# SCH_Orcon_MV_Control_2023-08-23.net
KiCad netlist of a schematic drawn in EasyEDA
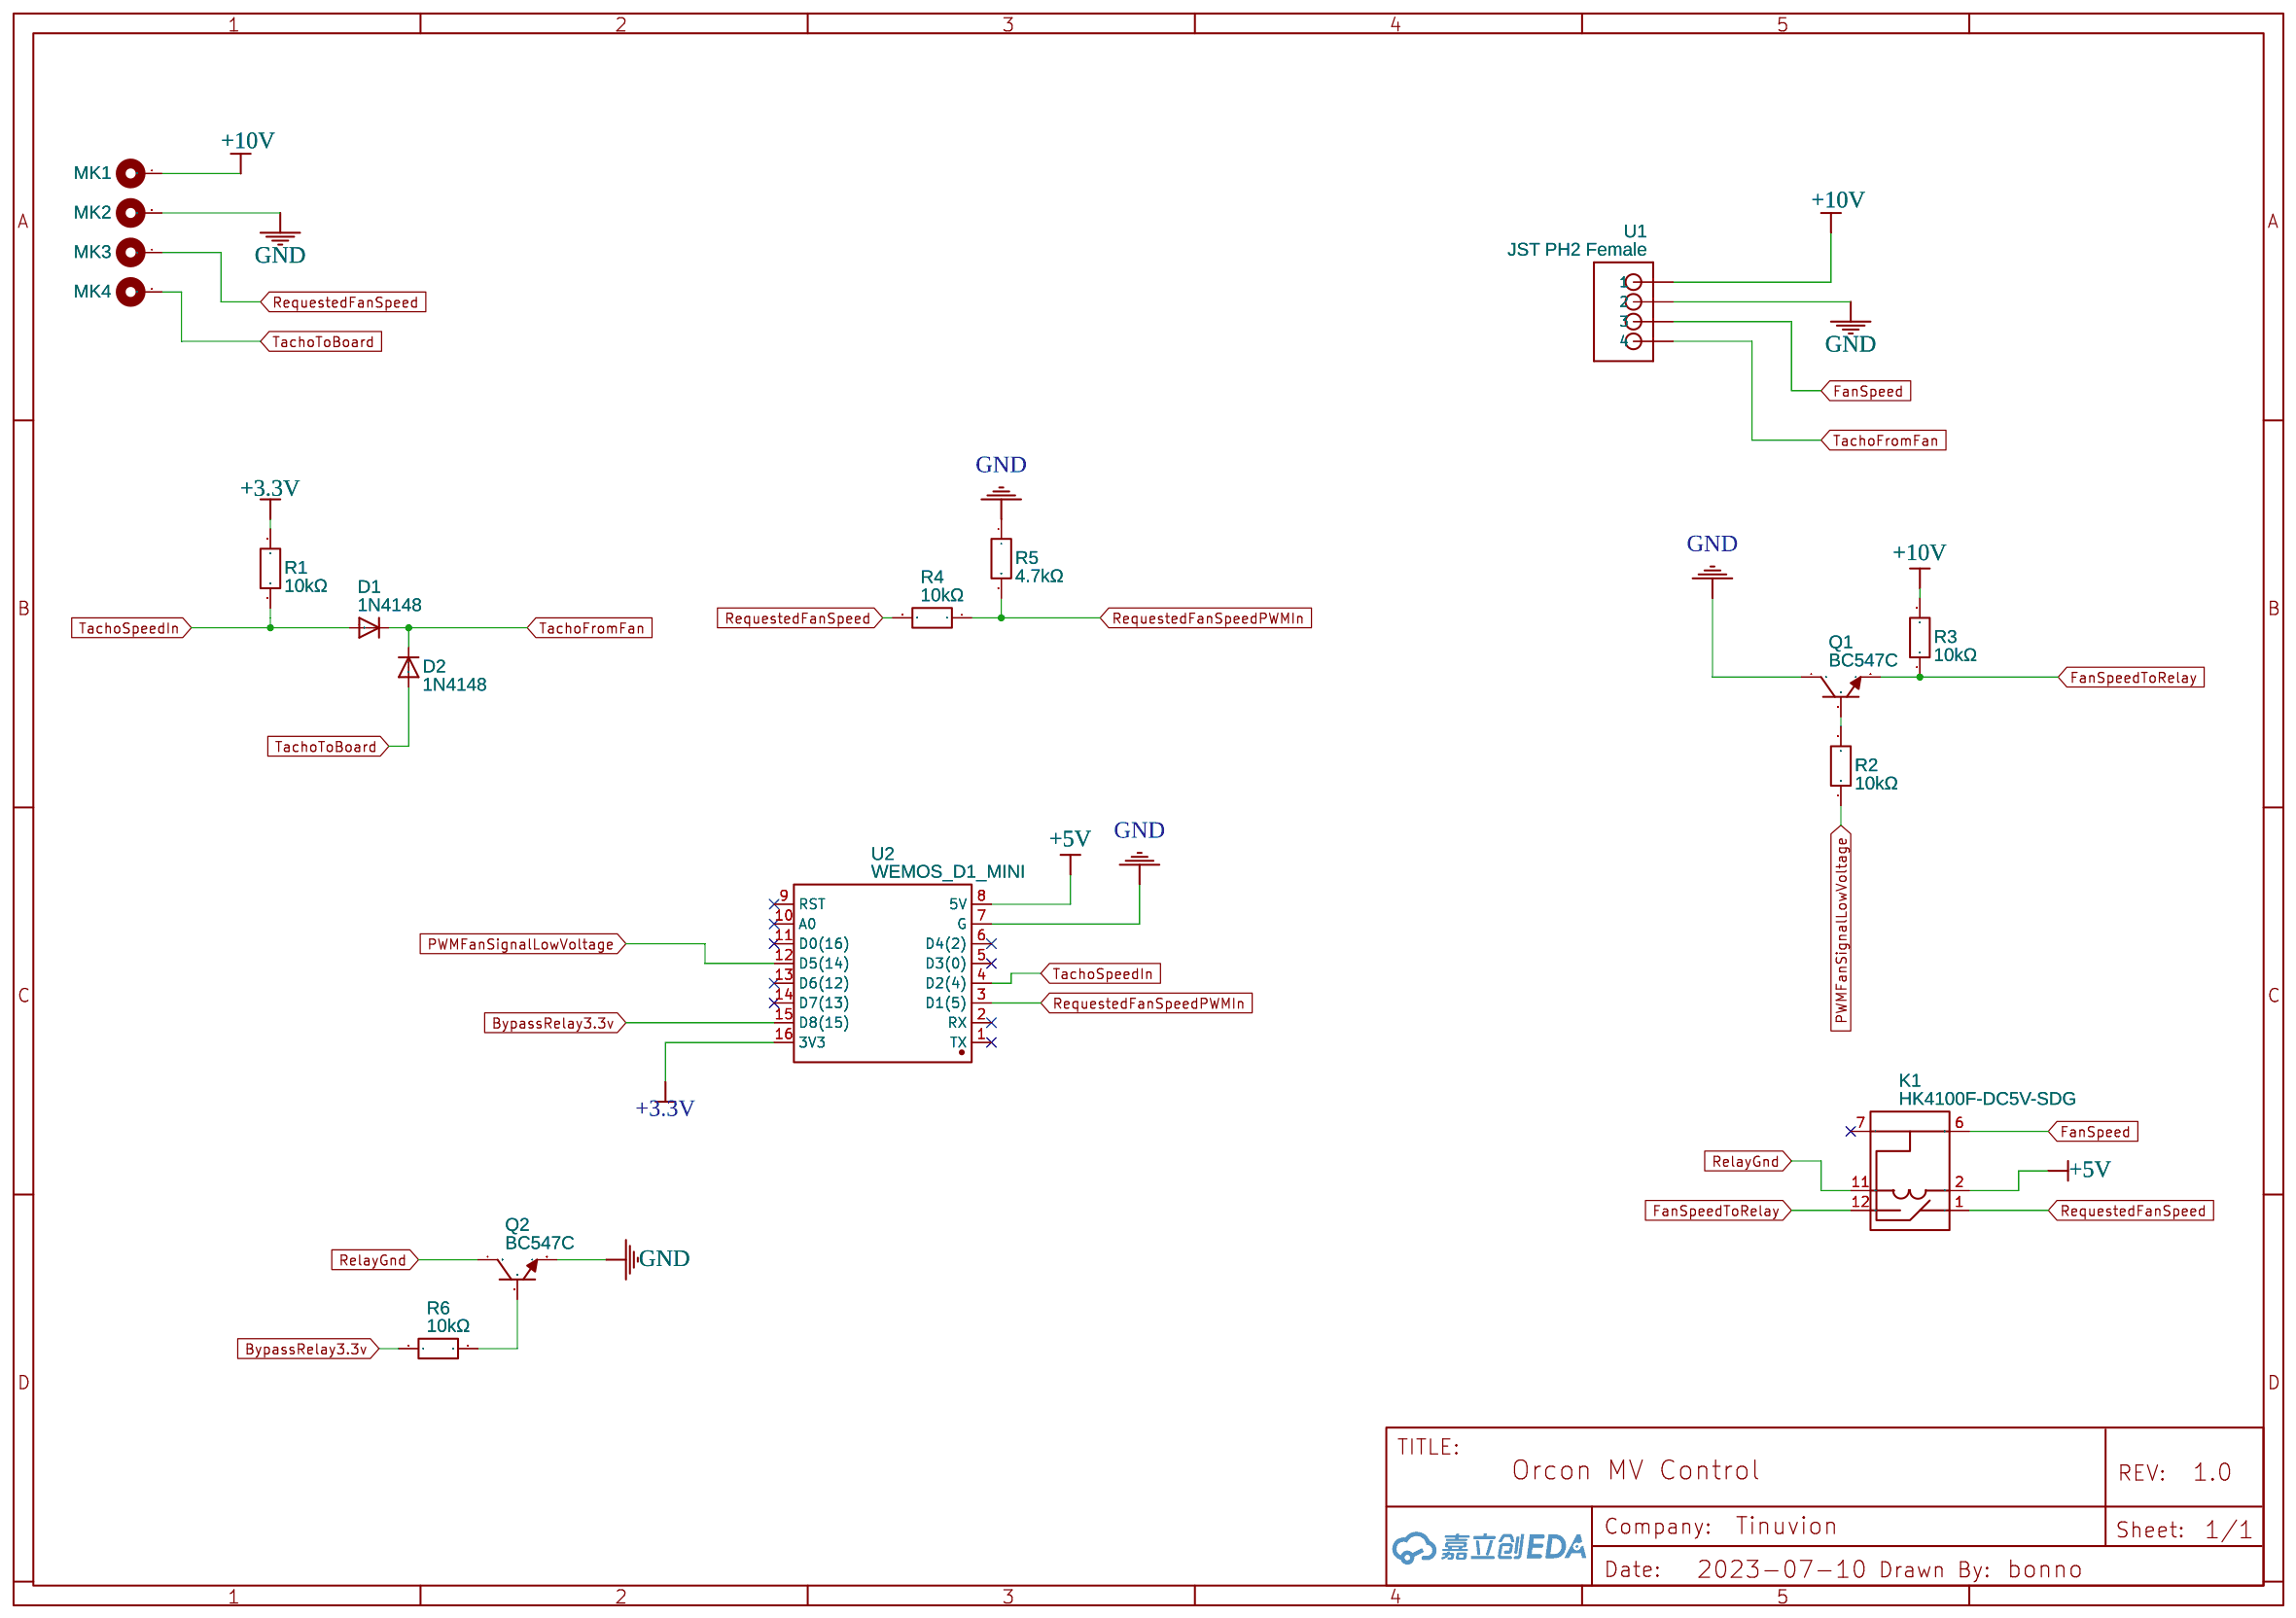
[diagram p0: schematic sheet]

(export (version "E")
  (design (tool "Eeschema 10.0.6"))
  (components
    (comp (ref "D1")
      (value "1N4148")
      (fields (field (name "Manufacturer") "ST(先科)"))
      (libsource (lib "") (part "DIODE_1"))
    )
    (comp (ref "D2")
      (value "1N4148")
      (fields (field (name "Manufacturer") "ST(先科)"))
      (libsource (lib "") (part "DIODE"))
    )
    (comp (ref "K1")
      (value "HK4100F-DC5V-SDG")
      (fields (field (name "Manufacturer") "汇科"))
      (libsource (lib "") (part "HK4100F-DC5V-SDG"))
    )
    (comp (ref "MK1") (value "Mounting_Hole_PAD") (libsource (lib "") (part "Mounting_Hole_PAD")))
    (comp (ref "MK2") (value "Mounting_Hole_PAD") (libsource (lib "") (part "Mounting_Hole_PAD")))
    (comp (ref "MK3") (value "Mounting_Hole_PAD") (libsource (lib "") (part "Mounting_Hole_PAD")))
    (comp (ref "MK4") (value "Mounting_Hole_PAD") (libsource (lib "") (part "Mounting_Hole_PAD")))
    (comp (ref "Q1")
      (value "BC547C")
      (fields (field (name "Manufacturer") "LGE"))
      (libsource (lib "") (part "BC547C"))
    )
    (comp (ref "Q2")
      (value "BC547C")
      (fields (field (name "Manufacturer") "LGE"))
      (libsource (lib "") (part "BC547C"))
    )
    (comp (ref "R1")
      (value "10kΩ")
      (fields (field (name "Manufacturer Part") "AR03BTD1002") (field (name "Manufacturer") "Viking(光颉)"))
      (libsource (lib "") (part "R_0603_EU"))
    )
    (comp (ref "R2")
      (value "10kΩ")
      (fields (field (name "Manufacturer Part") "AR03BTD1002") (field (name "Manufacturer") "Viking(光颉)"))
      (libsource (lib "") (part "R_0603_EU"))
    )
    (comp (ref "R3")
      (value "10kΩ")
      (fields (field (name "Manufacturer Part") "AR03BTD1002") (field (name "Manufacturer") "Viking(光颉)"))
      (libsource (lib "") (part "R_0603_EU"))
    )
    (comp (ref "R4")
      (value "10kΩ")
      (fields (field (name "Manufacturer Part") "AR03BTD1002") (field (name "Manufacturer") "Viking(光颉)"))
      (libsource (lib "") (part "R_0603_EU_2"))
    )
    (comp (ref "R5")
      (value "4.7kΩ")
      (fields (field (name "Manufacturer Part") "MR08X472 JTL") (field (name "Manufacturer") "Walsin(华新科)"))
      (libsource (lib "") (part "R_0603_EU_1"))
    )
    (comp (ref "R6")
      (value "10kΩ")
      (fields (field (name "Manufacturer Part") "AR03BTD1002") (field (name "Manufacturer") "Viking(光颉)"))
      (libsource (lib "") (part "R_0603_EU_2"))
    )
    (comp (ref "U1") (value "JST PH2 Female") (libsource (lib "") (part "JST-PH_4-PIN_HEADER")))
    (comp (ref "U2")
      (value "WEMOS_D1_MINI")
      (fields (field (name "Manufacturer Part") "Wemos_D1_mini_Pro4"))
      (libsource (lib "") (part "WEMOS_D1_MINI_PRO4"))
    )
  )
  (nets
    (net (code "1") (name "+3.3V") (class "Default")
      (node (ref "R1") (pin "2") (pinfunction "2_2") (pintype "unspecified"))
      (node (ref "U2") (pin "16") (pinfunction "3V3_16") (pintype "unspecified"))
    )
    (net (code "2") (name "+5V") (class "Default")
      (node (ref "K1") (pin "2") (pinfunction "2_2") (pintype "unspecified"))
      (node (ref "U2") (pin "8") (pinfunction "5V_8") (pintype "unspecified"))
    )
    (net (code "3") (name "+10V") (class "Default")
      (node (ref "MK1") (pin "1") (pinfunction "1_1") (pintype "input"))
      (node (ref "R3") (pin "2") (pinfunction "2_2") (pintype "unspecified"))
      (node (ref "U1") (pin "P1") (pinfunction "1_P1") (pintype "unspecified"))
    )
    (net (code "4") (name "BypassRelay3.3v") (class "Default")
      (node (ref "R6") (pin "2") (pinfunction "2_2") (pintype "unspecified"))
      (node (ref "U2") (pin "15") (pinfunction "D8(15)_15") (pintype "unspecified"))
    )
    (net (code "5") (name "FanSpeed") (class "Default")
      (node (ref "K1") (pin "6") (pinfunction "6_6") (pintype "unspecified"))
      (node (ref "U1") (pin "P3") (pinfunction "3_P3") (pintype "unspecified"))
    )
    (net (code "6") (name "FanSpeedToRelay") (class "Default")
      (node (ref "K1") (pin "12") (pinfunction "12_12") (pintype "unspecified"))
      (node (ref "Q1") (pin "3") (pinfunction "E_3") (pintype "input"))
      (node (ref "R3") (pin "1") (pinfunction "1_1") (pintype "unspecified"))
    )
    (net (code "7") (name "GND") (class "Default")
      (node (ref "MK2") (pin "1") (pinfunction "1_1") (pintype "input"))
      (node (ref "Q1") (pin "1") (pinfunction "C_1") (pintype "input"))
      (node (ref "Q2") (pin "3") (pinfunction "E_3") (pintype "input"))
      (node (ref "R5") (pin "1") (pinfunction "1_1") (pintype "unspecified"))
      (node (ref "U1") (pin "P2") (pinfunction "2_P2") (pintype "unspecified"))
      (node (ref "U2") (pin "7") (pinfunction "G_7") (pintype "unspecified"))
    )
    (net (code "8") (name "Net-(Q1-B)") (class "Default")
      (node (ref "Q1") (pin "2") (pinfunction "B_2") (pintype "input"))
      (node (ref "R2") (pin "2") (pinfunction "2_2") (pintype "unspecified"))
    )
    (net (code "9") (name "Net-(Q2-B)") (class "Default")
      (node (ref "Q2") (pin "2") (pinfunction "B_2") (pintype "input"))
      (node (ref "R6") (pin "1") (pinfunction "1_1") (pintype "unspecified"))
    )
    (net (code "10") (name "PWMFanSignalLowVoltage") (class "Default")
      (node (ref "R2") (pin "1") (pinfunction "1_1") (pintype "unspecified"))
      (node (ref "U2") (pin "12") (pinfunction "D5(14)_12") (pintype "unspecified"))
    )
    (net (code "11") (name "RelayGnd") (class "Default")
      (node (ref "K1") (pin "11") (pinfunction "11_11") (pintype "unspecified"))
      (node (ref "Q2") (pin "1") (pinfunction "C_1") (pintype "input"))
    )
    (net (code "12") (name "RequestedFanSpeed") (class "Default")
      (node (ref "K1") (pin "1") (pinfunction "1_1") (pintype "unspecified"))
      (node (ref "MK3") (pin "1") (pinfunction "1_1") (pintype "input"))
      (node (ref "R4") (pin "2") (pinfunction "2_2") (pintype "unspecified"))
    )
    (net (code "13") (name "RequestedFanSpeedPWMIn") (class "Default")
      (node (ref "R4") (pin "1") (pinfunction "1_1") (pintype "unspecified"))
      (node (ref "R5") (pin "2") (pinfunction "2_2") (pintype "unspecified"))
      (node (ref "U2") (pin "3") (pinfunction "D1(5)_3") (pintype "unspecified"))
    )
    (net (code "14") (name "TachoFromFan") (class "Default")
      (node (ref "D1") (pin "C") (pinfunction "C_C") (pintype "unspecified"))
      (node (ref "D2") (pin "C") (pinfunction "C_C") (pintype "unspecified"))
      (node (ref "U1") (pin "P4") (pinfunction "4_P4") (pintype "unspecified"))
    )
    (net (code "15") (name "TachoSpeedIn") (class "Default")
      (node (ref "D1") (pin "A") (pinfunction "A_A") (pintype "unspecified"))
      (node (ref "R1") (pin "1") (pinfunction "1_1") (pintype "unspecified"))
      (node (ref "U2") (pin "4") (pinfunction "D2(4)_4") (pintype "unspecified"))
    )
    (net (code "16") (name "TachoToBoard") (class "Default")
      (node (ref "D2") (pin "A") (pinfunction "A_A") (pintype "unspecified"))
      (node (ref "MK4") (pin "1") (pinfunction "1_1") (pintype "input"))
    )
    (net (code "17") (name "unconnected-(K1-Pad7)") (class "Default")
      (node (ref "K1") (pin "7") (pinfunction "7_7") (pintype "unspecified+no_connect"))
    )
    (net (code "18") (name "unconnected-(U2-A0-Pad10)") (class "Default")
      (node (ref "U2") (pin "10") (pinfunction "A0_10") (pintype "unspecified+no_connect"))
    )
    (net (code "19") (name "unconnected-(U2-D0(16)-Pad11)") (class "Default")
      (node (ref "U2") (pin "11") (pinfunction "D0(16)_11") (pintype "unspecified+no_connect"))
    )
    (net (code "20") (name "unconnected-(U2-D3(0)-Pad5)") (class "Default")
      (node (ref "U2") (pin "5") (pinfunction "D3(0)_5") (pintype "unspecified+no_connect"))
    )
    (net (code "21") (name "unconnected-(U2-D4(2)-Pad6)") (class "Default")
      (node (ref "U2") (pin "6") (pinfunction "D4(2)_6") (pintype "unspecified+no_connect"))
    )
    (net (code "22") (name "unconnected-(U2-D6(12)-Pad13)") (class "Default")
      (node (ref "U2") (pin "13") (pinfunction "D6(12)_13") (pintype "unspecified+no_connect"))
    )
    (net (code "23") (name "unconnected-(U2-D7(13)-Pad14)") (class "Default")
      (node (ref "U2") (pin "14") (pinfunction "D7(13)_14") (pintype "unspecified+no_connect"))
    )
    (net (code "24") (name "unconnected-(U2-RST-Pad9)") (class "Default")
      (node (ref "U2") (pin "9") (pinfunction "RST_9") (pintype "unspecified+no_connect"))
    )
    (net (code "25") (name "unconnected-(U2-RX-Pad2)") (class "Default")
      (node (ref "U2") (pin "2") (pinfunction "RX_2") (pintype "unspecified+no_connect"))
    )
    (net (code "26") (name "unconnected-(U2-TX-Pad1)") (class "Default")
      (node (ref "U2") (pin "1") (pinfunction "TX_1") (pintype "unspecified+no_connect"))
    )
  )
)
